# bpod_stepper_1_5_2.net
KiCad netlist of a schematic drawn in EAGLE
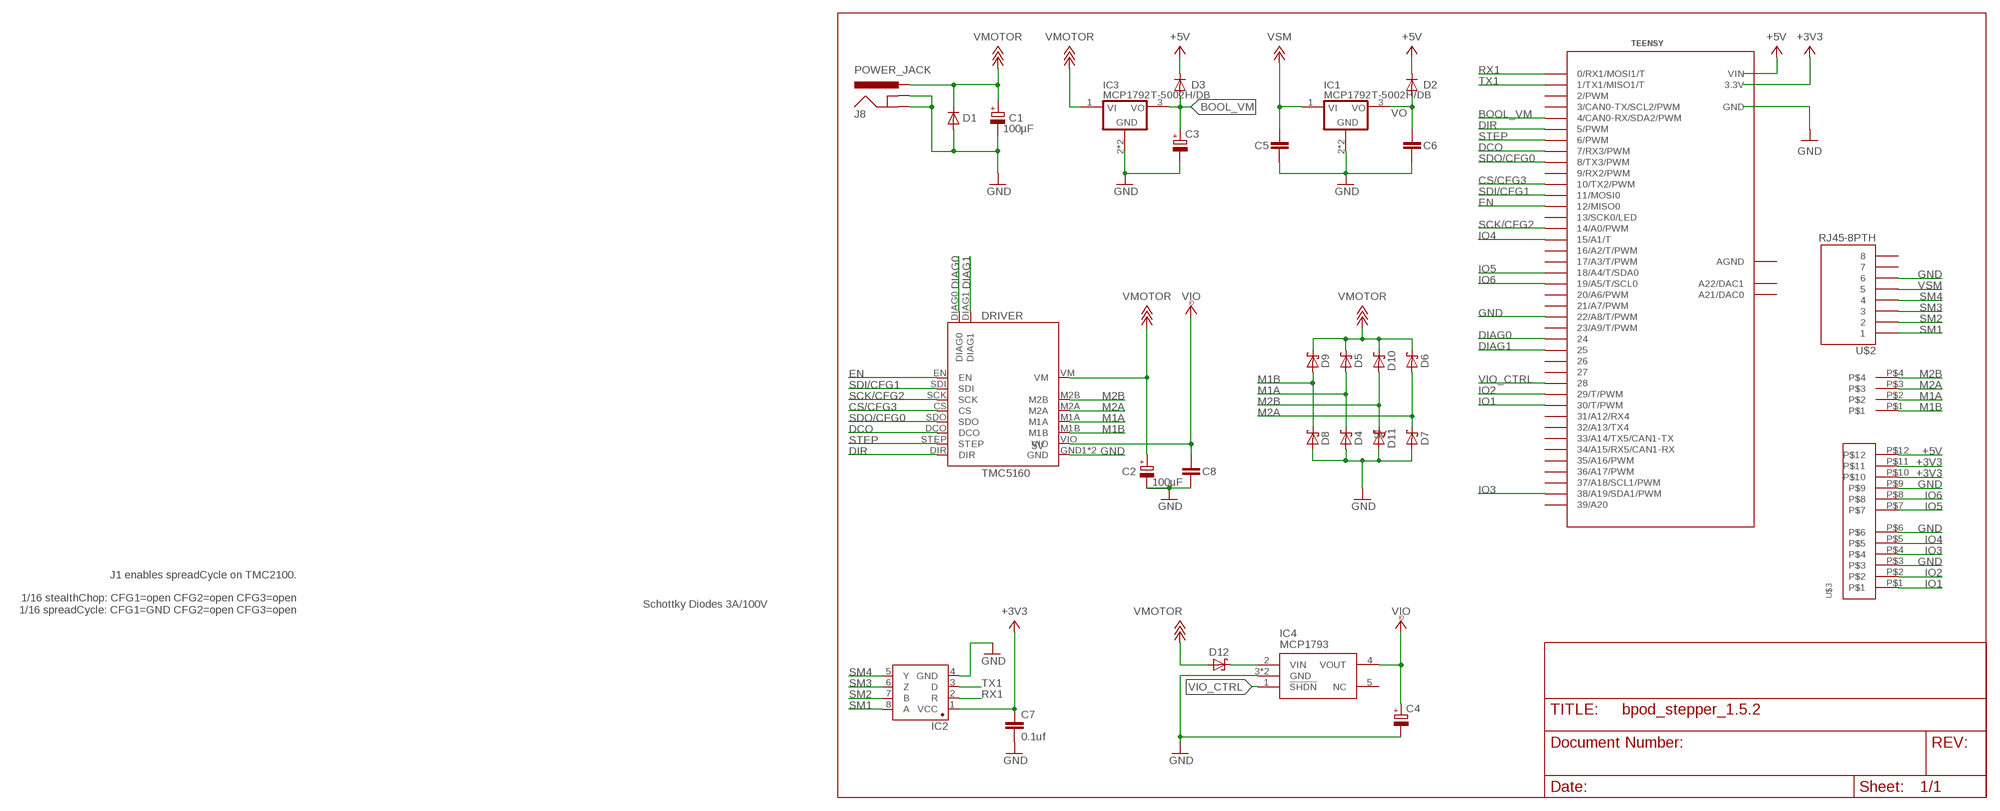
[diagram p0: schematic, sheet 1]

(export (version "E")
  (design (tool "Eeschema 10.0.6"))
  (components
    (comp (ref "C1")
      (value "100µF")
      (footprint "eagle-import:PANASONIC_G")
      (libsource (lib "eagle-import") (part "CPOL-EUG"))
    )
    (comp (ref "C2")
      (value "100µF")
      (footprint "eagle-import:PANASONIC_G")
      (libsource (lib "eagle-import") (part "CPOL-EUG"))
    )
    (comp (ref "C3")
      (value "CPOL-EUB")
      (footprint "eagle-import:PANASONIC_B")
      (libsource (lib "eagle-import") (part "CPOL-EUB"))
    )
    (comp (ref "C4")
      (value "CPOL-EUB")
      (footprint "eagle-import:PANASONIC_B")
      (libsource (lib "eagle-import") (part "CPOL-EUB"))
    )
    (comp (ref "C5")
      (value "0.1uf")
      (footprint "eagle-import:1206@1")
      (libsource (lib "eagle-import") (part "CAP1206"))
    )
    (comp (ref "C6")
      (value "0.1uf")
      (footprint "eagle-import:1206@1")
      (libsource (lib "eagle-import") (part "CAP1206"))
    )
    (comp (ref "C7")
      (value "0.1uf")
      (footprint "eagle-import:1206@1")
      (libsource (lib "eagle-import") (part "CAP1206"))
    )
    (comp (ref "C8")
      (value "100nf")
      (footprint "eagle-import:1206@1")
      (libsource (lib "eagle-import") (part "CAP1206"))
    )
    (comp (ref "D1")
      (value "DIODE-DO214AA")
      (footprint "eagle-import:DO214AA")
      (libsource (lib "eagle-import") (part "DIODE-DO214AA"))
    )
    (comp (ref "D2")
      (value "MBR0520LT")
      (footprint "eagle-import:SOD123")
      (libsource (lib "eagle-import") (part "MBR0520LT"))
    )
    (comp (ref "D3")
      (value "MBR0520LT")
      (footprint "eagle-import:SOD123")
      (libsource (lib "eagle-import") (part "MBR0520LT"))
    )
    (comp (ref "D4")
      (value "S310FA")
      (footprint "eagle-import:SOD123")
      (libsource (lib "eagle-import") (part "D_SCHOTTKY-SOD123"))
    )
    (comp (ref "D5")
      (value "S310FA")
      (footprint "eagle-import:SOD123")
      (libsource (lib "eagle-import") (part "D_SCHOTTKY-SOD123"))
    )
    (comp (ref "D6")
      (value "S310FA")
      (footprint "eagle-import:SOD123")
      (libsource (lib "eagle-import") (part "D_SCHOTTKY-SOD123"))
    )
    (comp (ref "D7")
      (value "S310FA")
      (footprint "eagle-import:SOD123")
      (libsource (lib "eagle-import") (part "D_SCHOTTKY-SOD123"))
    )
    (comp (ref "D8")
      (value "S310FA")
      (footprint "eagle-import:SOD123")
      (libsource (lib "eagle-import") (part "D_SCHOTTKY-SOD123"))
    )
    (comp (ref "D9")
      (value "S310FA")
      (footprint "eagle-import:SOD123")
      (libsource (lib "eagle-import") (part "D_SCHOTTKY-SOD123"))
    )
    (comp (ref "D10")
      (value "S310FA")
      (footprint "eagle-import:SOD123")
      (libsource (lib "eagle-import") (part "D_SCHOTTKY-SOD123"))
    )
    (comp (ref "D11")
      (value "S310FA")
      (footprint "eagle-import:SOD123")
      (libsource (lib "eagle-import") (part "D_SCHOTTKY-SOD123"))
    )
    (comp (ref "D12")
      (value "S310FA")
      (footprint "eagle-import:SOD123")
      (libsource (lib "eagle-import") (part "D_SCHOTTKY-SOD123"))
    )
    (comp (ref "DRIVER")
      (value "TMC5160")
      (footprint "eagle-import:TMC5160")
      (libsource (lib "eagle-import") (part "TMC5160"))
    )
    (comp (ref "IC1")
      (value "MCP1792T-5002H/DB")
      (footprint "eagle-import:SOT223")
      (libsource (lib "eagle-import") (part "MCP1792T-5002H/DB"))
    )
    (comp (ref "IC2")
      (value "SN65HVD31DR")
      (footprint "eagle-import:SO08")
      (libsource (lib "eagle-import") (part "SN65HVD31DR"))
    )
    (comp (ref "IC3")
      (value "MCP1792T-5002H/DB")
      (footprint "eagle-import:SOT223")
      (libsource (lib "eagle-import") (part "MCP1792T-5002H/DB"))
    )
    (comp (ref "IC4")
      (value "MCP1793")
      (footprint "eagle-import:SOT223-5")
      (libsource (lib "eagle-import") (part "MCP1793_SOT223-5"))
    )
    (comp (ref "J8")
      (value "POWER_JACK")
      (footprint "eagle-import:POWER_JACK_PTH")
      (libsource (lib "eagle-import") (part "POWER_JACK"))
    )
    (comp (ref "TEENSY")
      (value "TEENSY_3.6_DIL")
      (footprint "eagle-import:TEENSY_3.6_DIL")
      (libsource (lib "eagle-import") (part "TEENSY_3.6_DIL"))
    )
    (comp (ref "U$2")
      (value "RJ45-8PTH")
      (footprint "eagle-import:RJ45-8")
      (libsource (lib "eagle-import") (part "RJ45-8PTH"))
    )
    (comp (ref "U$3")
      (value "12POS_MOLEX_SOCKET")
      (footprint "eagle-import:12POS_MOLEX_SOCKET")
      (libsource (lib "eagle-import") (part "12POS_MOLEX_SOCKET"))
    )
    (comp (ref "U$4")
      (value "MOLEX395221004")
      (footprint "eagle-import:MOLEX395221004")
      (libsource (lib "eagle-import") (part "MOLEX395221004"))
    )
  )
  (nets
    (net (code "1") (name "+3V3") (class "Default")
      (node (ref "C7") (pin "1") (pinfunction "1_1") (pintype "passive"))
      (node (ref "IC2") (pin "1") (pinfunction "VCC_1") (pintype "bidirectional"))
      (node (ref "TEENSY") (pin "3.3V") (pinfunction "3.3V_3.3V") (pintype "power_in"))
      (node (ref "TEENSY") (pin "3.3V3") (pinfunction "3.3V_3.3V3") (pintype "power_in"))
      (node (ref "U$3") (pin "P$10") (pinfunction "P$10_P$10") (pintype "bidirectional"))
      (node (ref "U$3") (pin "P$11") (pinfunction "P$11_P$11") (pintype "bidirectional"))
    )
    (net (code "2") (name "+5V") (class "Default")
      (node (ref "D2") (pin "C") (pinfunction "C_C") (pintype "passive"))
      (node (ref "D3") (pin "C") (pinfunction "C_C") (pintype "passive"))
      (node (ref "TEENSY") (pin "VIN") (pinfunction "VIN_VIN") (pintype "power_in"))
      (node (ref "U$3") (pin "P$12") (pinfunction "P$12_P$12") (pintype "bidirectional"))
    )
    (net (code "3") (name "+12V") (class "Default")
      (node (ref "C5") (pin "2") (pinfunction "2_2") (pintype "passive"))
      (node (ref "IC1") (pin "1") (pinfunction "VI_1") (pintype "power_in"))
      (node (ref "U$2") (pin "5") (pinfunction "5_5") (pintype "bidirectional"))
    )
    (net (code "4") (name "+18V") (class "Default")
      (node (ref "C1") (pin "+") (pinfunction "+_+") (pintype "passive"))
      (node (ref "C2") (pin "+") (pinfunction "+_+") (pintype "passive"))
      (node (ref "D1") (pin "C") (pinfunction "C_C") (pintype "passive"))
      (node (ref "D10") (pin "C") (pinfunction "C_C") (pintype "passive"))
      (node (ref "D12") (pin "A") (pinfunction "A_A") (pintype "passive"))
      (node (ref "D5") (pin "C") (pinfunction "C_C") (pintype "passive"))
      (node (ref "D6") (pin "C") (pinfunction "C_C") (pintype "passive"))
      (node (ref "D9") (pin "C") (pinfunction "C_C") (pintype "passive"))
      (node (ref "DRIVER") (pin "VM") (pinfunction "VM_VM") (pintype "power_in"))
      (node (ref "IC3") (pin "1") (pinfunction "VI_1") (pintype "power_in"))
      (node (ref "J8") (pin "PWR") (pinfunction "PWR_PWR") (pintype "bidirectional"))
    )
    (net (code "5") (name "/AGND") (class "Default")
      (node (ref "TEENSY") (pin "AGND") (pinfunction "AGND_AGND") (pintype "power_in"))
    )
    (net (code "6") (name "/CS{slash}CFG3") (class "Default")
      (node (ref "DRIVER") (pin "CS") (pinfunction "CS_CS") (pintype "passive"))
      (node (ref "TEENSY") (pin "10") (pinfunction "10/TX2/PWM_10") (pintype "bidirectional"))
    )
    (net (code "7") (name "/DCO") (class "Default")
      (node (ref "DRIVER") (pin "DCO") (pinfunction "DCO_DCO") (pintype "passive"))
      (node (ref "TEENSY") (pin "7") (pinfunction "7/RX3/PWM_7") (pintype "bidirectional"))
    )
    (net (code "8") (name "/DIAG0") (class "Default")
      (node (ref "DRIVER") (pin "DIAG0") (pinfunction "DIAG0_DIAG0") (pintype "passive"))
      (node (ref "TEENSY") (pin "24") (pinfunction "24_24") (pintype "bidirectional"))
    )
    (net (code "9") (name "/DIAG1") (class "Default")
      (node (ref "DRIVER") (pin "DIAG1") (pinfunction "DIAG1_DIAG1") (pintype "passive"))
      (node (ref "TEENSY") (pin "25") (pinfunction "25_25") (pintype "bidirectional"))
    )
    (net (code "10") (name "/DIR") (class "Default")
      (node (ref "DRIVER") (pin "DIR") (pinfunction "DIR_DIR") (pintype "input"))
      (node (ref "TEENSY") (pin "5") (pinfunction "5/PWM_5") (pintype "bidirectional"))
    )
    (net (code "11") (name "/EN") (class "Default")
      (node (ref "DRIVER") (pin "EN") (pinfunction "EN_EN") (pintype "passive"))
      (node (ref "TEENSY") (pin "12") (pinfunction "12/MISO0_12") (pintype "bidirectional"))
    )
    (net (code "12") (name "/IO1") (class "Default")
      (node (ref "TEENSY") (pin "30") (pinfunction "30/T/PWM_30") (pintype "bidirectional"))
      (node (ref "U$3") (pin "P$1") (pinfunction "P$1_P$1") (pintype "bidirectional"))
    )
    (net (code "13") (name "/IO2") (class "Default")
      (node (ref "TEENSY") (pin "29") (pinfunction "29/T/PWM_29") (pintype "bidirectional"))
      (node (ref "U$3") (pin "P$2") (pinfunction "P$2_P$2") (pintype "bidirectional"))
    )
    (net (code "14") (name "/IO3") (class "Default")
      (node (ref "TEENSY") (pin "38/A19") (pinfunction "38/A19/SDA1/PWM_38/A19") (pintype "bidirectional"))
      (node (ref "U$3") (pin "P$4") (pinfunction "P$4_P$4") (pintype "bidirectional"))
    )
    (net (code "15") (name "/IO4") (class "Default")
      (node (ref "TEENSY") (pin "15/A1") (pinfunction "15/A1/T_15/A1") (pintype "bidirectional"))
      (node (ref "U$3") (pin "P$5") (pinfunction "P$5_P$5") (pintype "bidirectional"))
    )
    (net (code "16") (name "/IO5") (class "Default")
      (node (ref "TEENSY") (pin "18/A4") (pinfunction "18/A4/T/SDA0_18/A4") (pintype "bidirectional"))
      (node (ref "U$3") (pin "P$7") (pinfunction "P$7_P$7") (pintype "bidirectional"))
    )
    (net (code "17") (name "/IO6") (class "Default")
      (node (ref "TEENSY") (pin "19/A5") (pinfunction "19/A5/T/SCL0_19/A5") (pintype "bidirectional"))
      (node (ref "U$3") (pin "P$8") (pinfunction "P$8_P$8") (pintype "bidirectional"))
    )
    (net (code "18") (name "/M1A") (class "Default")
      (node (ref "D4") (pin "C") (pinfunction "C_C") (pintype "passive"))
      (node (ref "D5") (pin "A") (pinfunction "A_A") (pintype "passive"))
      (node (ref "DRIVER") (pin "M1A") (pinfunction "M1A_M1A") (pintype "output"))
      (node (ref "U$4") (pin "P$2") (pinfunction "P$2_P$2") (pintype "bidirectional"))
    )
    (net (code "19") (name "/M1B") (class "Default")
      (node (ref "D8") (pin "C") (pinfunction "C_C") (pintype "passive"))
      (node (ref "D9") (pin "A") (pinfunction "A_A") (pintype "passive"))
      (node (ref "DRIVER") (pin "M1B") (pinfunction "M1B_M1B") (pintype "output"))
      (node (ref "U$4") (pin "P$1") (pinfunction "P$1_P$1") (pintype "bidirectional"))
    )
    (net (code "20") (name "/M2A") (class "Default")
      (node (ref "D6") (pin "A") (pinfunction "A_A") (pintype "passive"))
      (node (ref "D7") (pin "C") (pinfunction "C_C") (pintype "passive"))
      (node (ref "DRIVER") (pin "M2A") (pinfunction "M2A_M2A") (pintype "output"))
      (node (ref "U$4") (pin "P$3") (pinfunction "P$3_P$3") (pintype "bidirectional"))
    )
    (net (code "21") (name "/M2B") (class "Default")
      (node (ref "D10") (pin "A") (pinfunction "A_A") (pintype "passive"))
      (node (ref "D11") (pin "C") (pinfunction "C_C") (pintype "passive"))
      (node (ref "DRIVER") (pin "M2B") (pinfunction "M2B_M2B") (pintype "output"))
      (node (ref "U$4") (pin "P$4") (pinfunction "P$4_P$4") (pintype "bidirectional"))
    )
    (net (code "22") (name "/RX1") (class "Default")
      (node (ref "IC2") (pin "2") (pinfunction "R_2") (pintype "bidirectional"))
      (node (ref "TEENSY") (pin "0") (pinfunction "0/RX1/MOSI1/T_0") (pintype "bidirectional"))
    )
    (net (code "23") (name "/SCK{slash}CFG2") (class "Default")
      (node (ref "DRIVER") (pin "SCK") (pinfunction "SCK_SCK") (pintype "passive"))
      (node (ref "TEENSY") (pin "14/A0") (pinfunction "14/A0/PWM_14/A0") (pintype "bidirectional"))
    )
    (net (code "24") (name "/SDI{slash}CFG1") (class "Default")
      (node (ref "DRIVER") (pin "SDI") (pinfunction "SDI_SDI") (pintype "passive"))
      (node (ref "TEENSY") (pin "11") (pinfunction "11/MOSI0_11") (pintype "bidirectional"))
    )
    (net (code "25") (name "/SDO{slash}CFG0") (class "Default")
      (node (ref "DRIVER") (pin "SDO") (pinfunction "SDO_SDO") (pintype "passive"))
      (node (ref "TEENSY") (pin "8") (pinfunction "8/TX3/PWM_8") (pintype "bidirectional"))
    )
    (net (code "26") (name "/SM1") (class "Default")
      (node (ref "IC2") (pin "8") (pinfunction "A_8") (pintype "bidirectional"))
      (node (ref "U$2") (pin "1") (pinfunction "1_1") (pintype "bidirectional"))
    )
    (net (code "27") (name "/SM2") (class "Default")
      (node (ref "IC2") (pin "7") (pinfunction "B_7") (pintype "bidirectional"))
      (node (ref "U$2") (pin "2") (pinfunction "2_2") (pintype "bidirectional"))
    )
    (net (code "28") (name "/SM3") (class "Default")
      (node (ref "IC2") (pin "6") (pinfunction "Z_6") (pintype "bidirectional"))
      (node (ref "U$2") (pin "3") (pinfunction "3_3") (pintype "bidirectional"))
    )
    (net (code "29") (name "/SM4") (class "Default")
      (node (ref "IC2") (pin "5") (pinfunction "Y_5") (pintype "bidirectional"))
      (node (ref "U$2") (pin "4") (pinfunction "4_4") (pintype "bidirectional"))
    )
    (net (code "30") (name "/STEP") (class "Default")
      (node (ref "DRIVER") (pin "STEP") (pinfunction "STEP_STEP") (pintype "input"))
      (node (ref "TEENSY") (pin "6") (pinfunction "6/PWM_6") (pintype "bidirectional"))
    )
    (net (code "31") (name "/TX1") (class "Default")
      (node (ref "IC2") (pin "3") (pinfunction "D_3") (pintype "bidirectional"))
      (node (ref "TEENSY") (pin "1") (pinfunction "1/TX1/MISO1/T_1") (pintype "bidirectional"))
    )
    (net (code "32") (name "/VO") (class "Default")
      (node (ref "C6") (pin "2") (pinfunction "2_2") (pintype "passive"))
      (node (ref "D2") (pin "A") (pinfunction "A_A") (pintype "passive"))
      (node (ref "IC1") (pin "3") (pinfunction "VO_3") (pintype "passive"))
    )
    (net (code "33") (name "BOOL_VM") (class "Default")
      (node (ref "C3") (pin "+") (pinfunction "+_+") (pintype "passive"))
      (node (ref "D3") (pin "A") (pinfunction "A_A") (pintype "passive"))
      (node (ref "IC3") (pin "3") (pinfunction "VO_3") (pintype "passive"))
      (node (ref "TEENSY") (pin "4") (pinfunction "4/CAN0-RX/SDA2/PWM_4") (pintype "bidirectional"))
    )
    (net (code "34") (name "GND") (class "Default")
      (node (ref "C1") (pin "-") (pinfunction "-_-") (pintype "passive"))
      (node (ref "C2") (pin "-") (pinfunction "-_-") (pintype "passive"))
      (node (ref "C3") (pin "-") (pinfunction "-_-") (pintype "passive"))
      (node (ref "C4") (pin "-") (pinfunction "-_-") (pintype "passive"))
      (node (ref "C5") (pin "1") (pinfunction "1_1") (pintype "passive"))
      (node (ref "C6") (pin "1") (pinfunction "1_1") (pintype "passive"))
      (node (ref "C7") (pin "2") (pinfunction "2_2") (pintype "passive"))
      (node (ref "C8") (pin "2") (pinfunction "2_2") (pintype "passive"))
      (node (ref "D1") (pin "A") (pinfunction "A_A") (pintype "passive"))
      (node (ref "D11") (pin "A") (pinfunction "A_A") (pintype "passive"))
      (node (ref "D4") (pin "A") (pinfunction "A_A") (pintype "passive"))
      (node (ref "D7") (pin "A") (pinfunction "A_A") (pintype "passive"))
      (node (ref "D8") (pin "A") (pinfunction "A_A") (pintype "passive"))
      (node (ref "DRIVER") (pin "GND1") (pinfunction "GND_GND1") (pintype "power_in"))
      (node (ref "DRIVER") (pin "GND2") (pinfunction "GND_GND2") (pintype "power_in"))
      (node (ref "IC1") (pin "2") (pinfunction "GND_2") (pintype "power_in"))
      (node (ref "IC1") (pin "4") (pinfunction "GND_4") (pintype "power_in"))
      (node (ref "IC2") (pin "4") (pinfunction "GND_4") (pintype "bidirectional"))
      (node (ref "IC3") (pin "2") (pinfunction "GND_2") (pintype "power_in"))
      (node (ref "IC3") (pin "4") (pinfunction "GND_4") (pintype "power_in"))
      (node (ref "IC4") (pin "3") (pinfunction "GND_3") (pintype "bidirectional"))
      (node (ref "IC4") (pin "6") (pinfunction "GND_6") (pintype "bidirectional"))
      (node (ref "J8") (pin "GND") (pinfunction "GND_GND") (pintype "bidirectional"))
      (node (ref "J8") (pin "GNDBREAK") (pinfunction "GNDBREAK_GNDBREAK") (pintype "bidirectional"))
      (node (ref "TEENSY") (pin "22/A8") (pinfunction "22/A8/T/PWM_22/A8") (pintype "bidirectional"))
      (node (ref "TEENSY") (pin "GND") (pinfunction "GND_GND") (pintype "power_in"))
      (node (ref "TEENSY") (pin "GND1") (pinfunction "GND_GND1") (pintype "power_in"))
      (node (ref "U$2") (pin "6") (pinfunction "6_6") (pintype "bidirectional"))
      (node (ref "U$3") (pin "P$3") (pinfunction "P$3_P$3") (pintype "bidirectional"))
      (node (ref "U$3") (pin "P$6") (pinfunction "P$6_P$6") (pintype "bidirectional"))
      (node (ref "U$3") (pin "P$9") (pinfunction "P$9_P$9") (pintype "bidirectional"))
    )
    (net (code "35") (name "Net-(IC4-VIN)") (class "Default")
      (node (ref "D12") (pin "C") (pinfunction "C_C") (pintype "passive"))
      (node (ref "IC4") (pin "2") (pinfunction "VIN_2") (pintype "bidirectional"))
    )
    (net (code "36") (name "VCCIO") (class "Default")
      (node (ref "C4") (pin "+") (pinfunction "+_+") (pintype "passive"))
      (node (ref "C8") (pin "1") (pinfunction "1_1") (pintype "passive"))
      (node (ref "DRIVER") (pin "VIO") (pinfunction "VIO_VIO") (pintype "power_in"))
      (node (ref "IC4") (pin "4") (pinfunction "VOUT_4") (pintype "bidirectional"))
    )
    (net (code "37") (name "VIO_CTRL") (class "Default")
      (node (ref "IC4") (pin "1") (pinfunction "~{SHDN}_1") (pintype "bidirectional"))
      (node (ref "TEENSY") (pin "28") (pinfunction "28_28") (pintype "bidirectional"))
    )
    (net (code "38") (name "unconnected-(IC4-NC-Pad5)") (class "Default")
      (node (ref "IC4") (pin "5") (pinfunction "NC_5") (pintype "bidirectional"))
    )
    (net (code "39") (name "unconnected-(TEENSY-2{slash}PWM-Pad2)") (class "Default")
      (node (ref "TEENSY") (pin "2") (pinfunction "2/PWM_2") (pintype "bidirectional"))
    )
    (net (code "40") (name "unconnected-(TEENSY-3{slash}CAN0-TX{slash}SCL2{slash}PWM-Pad3)") (class "Default")
      (node (ref "TEENSY") (pin "3") (pinfunction "3/CAN0-TX/SCL2/PWM_3") (pintype "bidirectional"))
    )
    (net (code "41") (name "unconnected-(TEENSY-9{slash}RX2{slash}PWM-Pad9)") (class "Default")
      (node (ref "TEENSY") (pin "9") (pinfunction "9/RX2/PWM_9") (pintype "bidirectional"))
    )
    (net (code "42") (name "unconnected-(TEENSY-13{slash}SCK0{slash}LED-Pad13)") (class "Default")
      (node (ref "TEENSY") (pin "13") (pinfunction "13/SCK0/LED_13") (pintype "bidirectional"))
    )
    (net (code "43") (name "unconnected-(TEENSY-16{slash}A2{slash}T{slash}PWM-Pad16{slash}A2)") (class "Default")
      (node (ref "TEENSY") (pin "16/A2") (pinfunction "16/A2/T/PWM_16/A2") (pintype "bidirectional"))
    )
    (net (code "44") (name "unconnected-(TEENSY-17{slash}A3{slash}T{slash}PWM-Pad17{slash}A3)") (class "Default")
      (node (ref "TEENSY") (pin "17/A3") (pinfunction "17/A3/T/PWM_17/A3") (pintype "bidirectional"))
    )
    (net (code "45") (name "unconnected-(TEENSY-20{slash}A6{slash}PWM-Pad20{slash}A6)") (class "Default")
      (node (ref "TEENSY") (pin "20/A6") (pinfunction "20/A6/PWM_20/A6") (pintype "bidirectional"))
    )
    (net (code "46") (name "unconnected-(TEENSY-21{slash}A7{slash}PWM-Pad21{slash}A7)") (class "Default")
      (node (ref "TEENSY") (pin "21/A7") (pinfunction "21/A7/PWM_21/A7") (pintype "bidirectional"))
    )
    (net (code "47") (name "unconnected-(TEENSY-23{slash}A9{slash}T{slash}PWM-Pad23{slash}A9)") (class "Default")
      (node (ref "TEENSY") (pin "23/A9") (pinfunction "23/A9/T/PWM_23/A9") (pintype "bidirectional"))
    )
    (net (code "48") (name "unconnected-(TEENSY-31{slash}A12{slash}RX4-Pad31{slash}A12)") (class "Default")
      (node (ref "TEENSY") (pin "31/A12") (pinfunction "31/A12/RX4_31/A12") (pintype "bidirectional"))
    )
    (net (code "49") (name "unconnected-(TEENSY-32{slash}A13{slash}TX4-Pad32{slash}A13)") (class "Default")
      (node (ref "TEENSY") (pin "32/A13") (pinfunction "32/A13/TX4_32/A13") (pintype "bidirectional"))
    )
    (net (code "50") (name "unconnected-(TEENSY-33{slash}A14{slash}TX5{slash}CAN1-TX-Pad33{slash}A14)") (class "Default")
      (node (ref "TEENSY") (pin "33/A14") (pinfunction "33/A14/TX5/CAN1-TX_33/A14") (pintype "bidirectional"))
    )
    (net (code "51") (name "unconnected-(TEENSY-34{slash}A15{slash}RX5{slash}CAN1-RX-Pad34{slash}A15)") (class "Default")
      (node (ref "TEENSY") (pin "34/A15") (pinfunction "34/A15/RX5/CAN1-RX_34/A15") (pintype "bidirectional"))
    )
    (net (code "52") (name "unconnected-(TEENSY-35{slash}A16{slash}PWM-Pad35{slash}A16)") (class "Default")
      (node (ref "TEENSY") (pin "35/A16") (pinfunction "35/A16/PWM_35/A16") (pintype "bidirectional"))
    )
    (net (code "53") (name "unconnected-(TEENSY-36{slash}A17{slash}PWM-Pad36{slash}A17)") (class "Default")
      (node (ref "TEENSY") (pin "36/A17") (pinfunction "36/A17/PWM_36/A17") (pintype "bidirectional"))
    )
    (net (code "54") (name "unconnected-(TEENSY-37{slash}A18{slash}SCL1{slash}PWM-Pad37{slash}A18)") (class "Default")
      (node (ref "TEENSY") (pin "37/A18") (pinfunction "37/A18/SCL1/PWM_37/A18") (pintype "bidirectional"))
    )
    (net (code "55") (name "unconnected-(TEENSY-A21{slash}DAC0-PadA21)") (class "Default")
      (node (ref "TEENSY") (pin "A21") (pinfunction "A21/DAC0_A21") (pintype "bidirectional"))
    )
    (net (code "56") (name "unconnected-(TEENSY-A22{slash}DAC1-PadA22)") (class "Default")
      (node (ref "TEENSY") (pin "A22") (pinfunction "A22/DAC1_A22") (pintype "bidirectional"))
    )
    (net (code "57") (name "unconnected-(TEENSY-Pad26)") (class "Default")
      (node (ref "TEENSY") (pin "26") (pinfunction "26_26") (pintype "bidirectional"))
    )
    (net (code "58") (name "unconnected-(TEENSY-Pad27)") (class "Default")
      (node (ref "TEENSY") (pin "27") (pinfunction "27_27") (pintype "bidirectional"))
    )
    (net (code "59") (name "unconnected-(TEENSY-Pad39{slash}A20)") (class "Default")
      (node (ref "TEENSY") (pin "39/A20") (pinfunction "39/A20_39/A20") (pintype "bidirectional"))
    )
    (net (code "60") (name "unconnected-(U$2-Pad7)") (class "Default")
      (node (ref "U$2") (pin "7") (pinfunction "7_7") (pintype "bidirectional"))
    )
    (net (code "61") (name "unconnected-(U$2-Pad8)") (class "Default")
      (node (ref "U$2") (pin "8") (pinfunction "8_8") (pintype "bidirectional"))
    )
  )
)
